# FOC-MESC_mini.net
KiCad netlist of a schematic drawn in Altium Designer
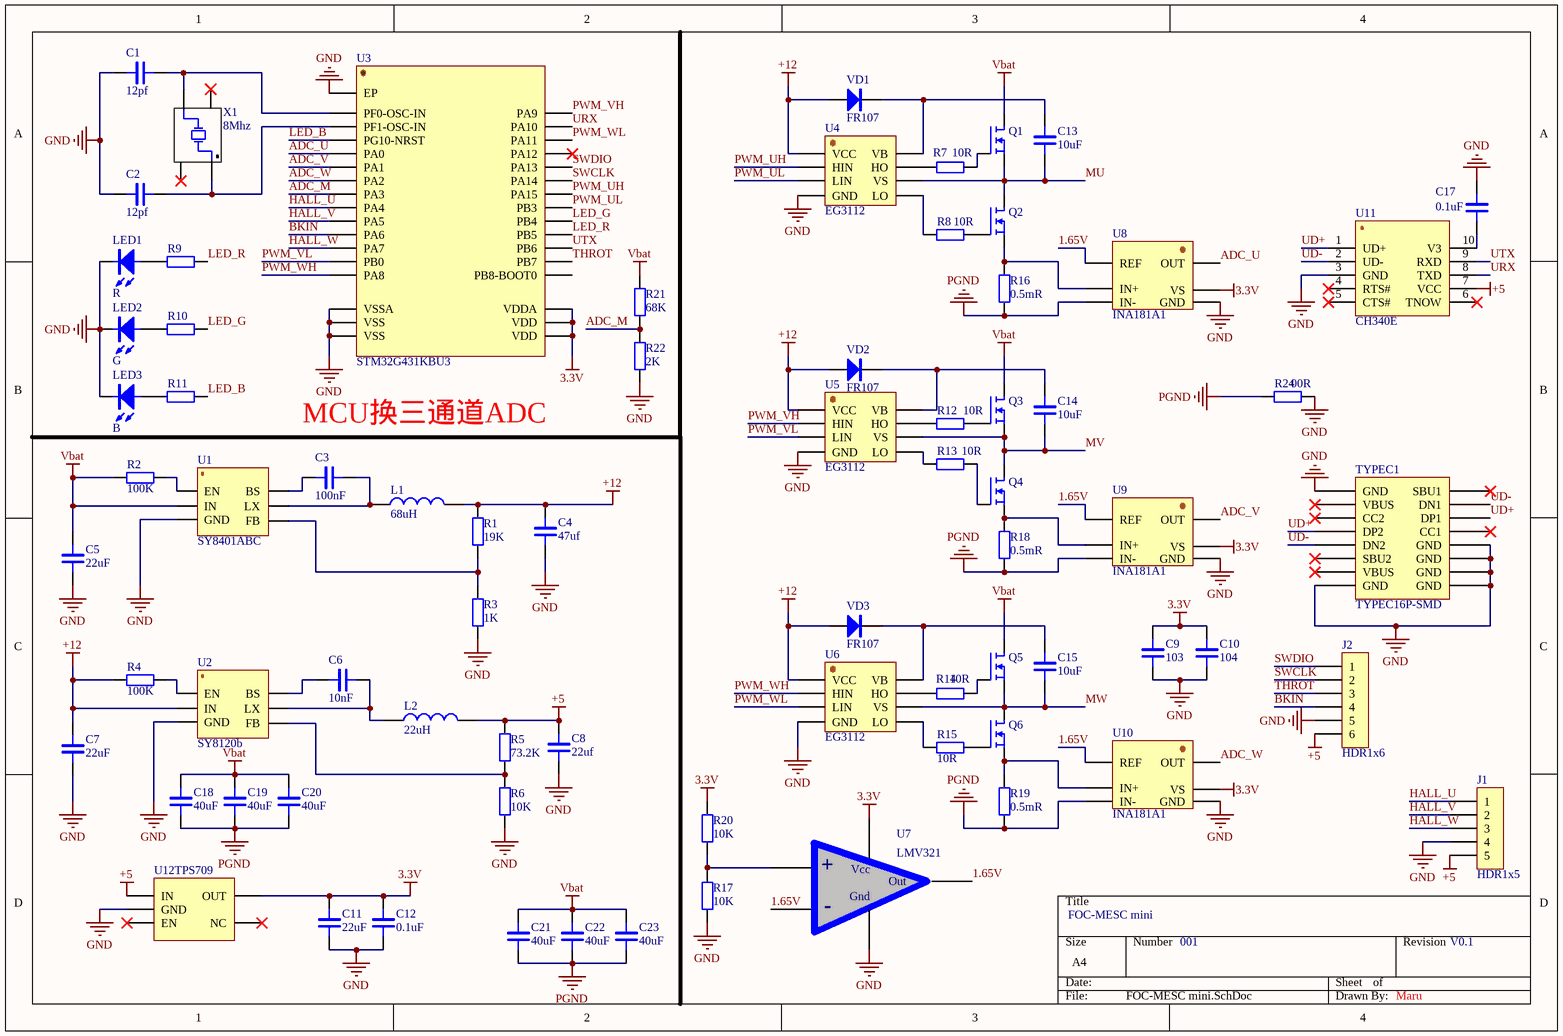
[diagram p0: FOC-MESC mini.SchDoc]

(export (version "E")
  (design (tool "Eeschema 10.0.6"))
  (components
    (comp (ref "C1")
      (value "12pf")
      (footprint "LC-0603_C")
      (description "Capacitor")
      (libsource (lib "General") (part "CAP"))
    )
    (comp (ref "C2")
      (value "12pf")
      (footprint "LC-0603_C")
      (description "Capacitor")
      (libsource (lib "General") (part "CAP"))
    )
    (comp (ref "C3")
      (value "100nF")
      (footprint "LC-0603_C")
      (description "Capacitor")
      (libsource (lib "General") (part "CAP"))
    )
    (comp (ref "C4")
      (value "47uf")
      (footprint "LC-0603_C")
      (description "Capacitor")
      (libsource (lib "General") (part "CAP"))
    )
    (comp (ref "C5")
      (value "22uF")
      (footprint "LC-0603_C")
      (description "Capacitor")
      (libsource (lib "General") (part "CAP"))
    )
    (comp (ref "C6")
      (value "10nF")
      (footprint "LC-0603_C")
      (description "Capacitor")
      (libsource (lib "General") (part "CAP"))
    )
    (comp (ref "C7")
      (value "22uF")
      (footprint "LC-0603_C")
      (description "Capacitor")
      (libsource (lib "General") (part "CAP"))
    )
    (comp (ref "C8")
      (value "22uf")
      (footprint "LC-0603_C")
      (description "Capacitor")
      (libsource (lib "General") (part "CAP"))
    )
    (comp (ref "C9")
      (value "103")
      (footprint "LC-0603_C")
      (description "Capacitor")
      (libsource (lib "General") (part "CAP"))
    )
    (comp (ref "C10")
      (value "104")
      (footprint "LC-0603_C")
      (description "Capacitor")
      (libsource (lib "General") (part "CAP"))
    )
    (comp (ref "C11")
      (value "22uF")
      (footprint "LC-0603_C")
      (description "Capacitor")
      (libsource (lib "General") (part "CAP"))
    )
    (comp (ref "C12")
      (value "0.1uF")
      (footprint "LC-0603_C")
      (description "Capacitor")
      (libsource (lib "General") (part "CAP"))
    )
    (comp (ref "C13")
      (value "10uF")
      (footprint "LC-0603_C")
      (description "Capacitor")
      (libsource (lib "General") (part "CAP"))
    )
    (comp (ref "C14")
      (value "10uF")
      (footprint "LC-0603_C")
      (description "Capacitor")
      (libsource (lib "General") (part "CAP"))
    )
    (comp (ref "C15")
      (value "10uF")
      (footprint "LC-0603_C")
      (description "Capacitor")
      (libsource (lib "General") (part "CAP"))
    )
    (comp (ref "C17")
      (value "0.1uF")
      (footprint "LC-0603_C")
      (description "Capacitor")
      (libsource (lib "General") (part "CAP"))
    )
    (comp (ref "C18")
      (value "40uF")
      (footprint "LC-1206_C")
      (description "Capacitor")
      (libsource (lib "General") (part "CAP"))
    )
    (comp (ref "C19")
      (value "40uF")
      (footprint "LC-1206_C")
      (description "Capacitor")
      (libsource (lib "General") (part "CAP"))
    )
    (comp (ref "C20")
      (value "40uF")
      (footprint "LC-1206_C")
      (description "Capacitor")
      (libsource (lib "General") (part "CAP"))
    )
    (comp (ref "C21")
      (value "40uF")
      (footprint "LC-1206_C")
      (description "Capacitor")
      (libsource (lib "General") (part "CAP"))
    )
    (comp (ref "C22")
      (value "40uF")
      (footprint "LC-1206_C")
      (description "Capacitor")
      (libsource (lib "General") (part "CAP"))
    )
    (comp (ref "C23")
      (value "40uF")
      (footprint "LC-1206_C")
      (description "Capacitor")
      (libsource (lib "General") (part "CAP"))
    )
    (comp (ref "J1")
      (value "HDR1x5")
      (footprint "HDR-1X5")
      (description "Connector")
      (libsource (lib "General") (part "HDR1x5"))
    )
    (comp (ref "J2")
      (value "HDR1x6")
      (footprint "PH2.0 S-W-6P")
      (description "Connector")
      (libsource (lib "General") (part "HDR1x6"))
    )
    (comp (ref "L1")
      (value "68uH")
      (footprint "CD31")
      (description "小功率贴片电感")
      (fields (field (name "版权归属") "源创客"))
      (libsource (lib "电阻-电容-电感") (part "L"))
    )
    (comp (ref "L2")
      (value "22uH")
      (footprint "CD31")
      (description "小功率贴片电感")
      (fields (field (name "版权归属") "源创客"))
      (libsource (lib "电阻-电容-电感") (part "L"))
    )
    (comp (ref "LED1") (value "R") (footprint "LED-0603") (libsource (lib "General") (part "LED")))
    (comp (ref "LED2")
      (value "G")
      (footprint "LED-0603")
      (description "LED")
      (libsource (lib "General") (part "LED"))
    )
    (comp (ref "LED3")
      (value "B")
      (footprint "LED-0603")
      (description "LED")
      (libsource (lib "General") (part "LED"))
    )
    (comp (ref "Q1")
      (value "N-MOSFET")
      (footprint "LC-DFN-8_5x6mm")
      (libsource (lib "General") (part "N-MOSFET"))
    )
    (comp (ref "Q2")
      (value "N-MOSFET")
      (footprint "LC-DFN-8_5x6mm")
      (libsource (lib "General") (part "N-MOSFET"))
    )
    (comp (ref "Q3")
      (value "N-MOSFET")
      (footprint "LC-DFN-8_5x6mm")
      (libsource (lib "General") (part "N-MOSFET"))
    )
    (comp (ref "Q4")
      (value "N-MOSFET")
      (footprint "LC-DFN-8_5x6mm")
      (libsource (lib "General") (part "N-MOSFET"))
    )
    (comp (ref "Q5")
      (value "N-MOSFET")
      (footprint "LC-DFN-8_5x6mm")
      (libsource (lib "General") (part "N-MOSFET"))
    )
    (comp (ref "Q6")
      (value "N-MOSFET")
      (footprint "LC-DFN-8_5x6mm")
      (libsource (lib "General") (part "N-MOSFET"))
    )
    (comp (ref "R1")
      (value "19K")
      (footprint "LC-0603_R")
      (description "Resistor")
      (libsource (lib "General") (part "RES"))
    )
    (comp (ref "R2")
      (value "100K")
      (footprint "LC-0603_R")
      (description "Resistor")
      (libsource (lib "") (part "RES_2"))
    )
    (comp (ref "R3")
      (value "1K")
      (footprint "LC-0603_R")
      (description "Resistor")
      (libsource (lib "General") (part "RES"))
    )
    (comp (ref "R4")
      (value "100K")
      (footprint "LC-0603_R")
      (description "Resistor")
      (libsource (lib "") (part "RES_2"))
    )
    (comp (ref "R5")
      (value "73.2K")
      (footprint "LC-0603_R")
      (description "Resistor")
      (libsource (lib "General") (part "RES"))
    )
    (comp (ref "R6")
      (value "10K")
      (footprint "LC-0603_R")
      (description "Resistor")
      (libsource (lib "General") (part "RES"))
    )
    (comp (ref "R7")
      (value "10R")
      (footprint "LC-0603_R")
      (description "Resistor")
      (libsource (lib "") (part "RES_1"))
    )
    (comp (ref "R8")
      (value "10R")
      (footprint "LC-0603_R")
      (description "Resistor")
      (libsource (lib "") (part "RES_1"))
    )
    (comp (ref "R9")
      (value "800R")
      (footprint "LC-0603_R")
      (description "Resistor")
      (libsource (lib "") (part "RES_1"))
    )
    (comp (ref "R10")
      (value "800R")
      (footprint "LC-0603_R")
      (description "Resistor")
      (libsource (lib "") (part "RES_1"))
    )
    (comp (ref "R11")
      (value "800R")
      (footprint "LC-0603_R")
      (description "Resistor")
      (libsource (lib "") (part "RES_1"))
    )
    (comp (ref "R12")
      (value "10R")
      (footprint "LC-0603_R")
      (description "Resistor")
      (libsource (lib "") (part "RES_1"))
    )
    (comp (ref "R13")
      (value "10R")
      (footprint "LC-0603_R")
      (description "Resistor")
      (libsource (lib "") (part "RES_1"))
    )
    (comp (ref "R14")
      (value "10R")
      (footprint "LC-0603_R")
      (description "Resistor")
      (libsource (lib "") (part "RES_1"))
    )
    (comp (ref "R15")
      (value "10R")
      (footprint "LC-0603_R")
      (description "Resistor")
      (libsource (lib "") (part "RES_1"))
    )
    (comp (ref "R16")
      (value "0.5mR")
      (footprint "LC-2512_R")
      (description "Resistor")
      (libsource (lib "General") (part "RES"))
    )
    (comp (ref "R17")
      (value "10K")
      (footprint "LC-0603_R")
      (description "Resistor")
      (libsource (lib "General") (part "RES"))
    )
    (comp (ref "R18")
      (value "0.5mR")
      (footprint "LC-2512_R")
      (description "Resistor")
      (libsource (lib "General") (part "RES"))
    )
    (comp (ref "R19")
      (value "0.5mR")
      (footprint "LC-2512_R")
      (description "Resistor")
      (libsource (lib "General") (part "RES"))
    )
    (comp (ref "R20")
      (value "10K")
      (footprint "LC-0603_R")
      (description "Resistor")
      (libsource (lib "General") (part "RES"))
    )
    (comp (ref "R21")
      (value "68K")
      (footprint "LC-0603_R")
      (description "Resistor")
      (libsource (lib "") (part "RES_3"))
    )
    (comp (ref "R22")
      (value "2K")
      (footprint "LC-0603_R")
      (description "Resistor")
      (libsource (lib "") (part "RES_3"))
    )
    (comp (ref "R24")
      (value "00R")
      (footprint "LC-1206_R")
      (description "Resistor")
      (libsource (lib "") (part "RES_1"))
    )
    (comp (ref "TYPEC1")
      (value "TYPEC16P-SMD")
      (footprint "TYPEC-16PIN DIP")
      (libsource (lib "General") (part "TYPEC16P-SMD"))
    )
    (comp (ref "U1")
      (value "SY8401ABC")
      (footprint "LC-SOT-23-6")
      (description "DC-DC")
      (libsource (lib "General") (part "SY8120b"))
    )
    (comp (ref "U2")
      (value "SY8120b")
      (footprint "LC-SOT-23-6")
      (description "DC-DC")
      (libsource (lib "General") (part "SY8120b"))
    )
    (comp (ref "U3")
      (value "STM32G431KBU3")
      (footprint "LC-QFN-32_7x7x065P")
      (libsource (lib "STM32系列单片机") (part "STM32G431KBU3"))
    )
    (comp (ref "U4")
      (value "EG3112")
      (footprint "LC-SOIC-8_150mil")
      (libsource (lib "General") (part "EG3112"))
    )
    (comp (ref "U5")
      (value "EG3112")
      (footprint "LC-SOIC-8_150mil")
      (libsource (lib "General") (part "EG3112"))
    )
    (comp (ref "U6")
      (value "EG3112")
      (footprint "LC-SOIC-8_150mil")
      (libsource (lib "General") (part "EG3112"))
    )
    (comp (ref "U7")
      (value "LMV321")
      (footprint "LC-SOT-23-5")
      (libsource (lib "General") (part "OPA-Single"))
    )
    (comp (ref "U8")
      (value "INA181A1")
      (footprint "LC-SOT-23-6")
      (description "40 倍")
      (libsource (lib "General") (part "INA181A1"))
    )
    (comp (ref "U9")
      (value "INA181A1")
      (footprint "LC-SOT-23-6")
      (description "40 倍")
      (libsource (lib "General") (part "INA181A1"))
    )
    (comp (ref "U10")
      (value "INA181A1")
      (footprint "LC-SOT-23-6")
      (description "40 倍")
      (libsource (lib "General") (part "INA181A1"))
    )
    (comp (ref "U11") (value "CH340E") (footprint "LC-MSOP-10") (libsource (lib "General") (part "CH340E")))
    (comp (ref "U12") (value "TPS709") (footprint "LC-SOT-23-5") (libsource (lib "General") (part "TPS709")))
    (comp (ref "VD1")
      (value "FR107")
      (footprint "LC-SOD-123F")
      (description "快恢复整流二极管")
      (fields (field (name "版权归属") "源创客"))
      (libsource (lib "二极管-整流桥") (part "FR107"))
    )
    (comp (ref "VD2")
      (value "FR107")
      (footprint "LC-SOD-123F")
      (description "快恢复整流二极管")
      (fields (field (name "版权归属") "源创客"))
      (libsource (lib "二极管-整流桥") (part "FR107"))
    )
    (comp (ref "VD3")
      (value "FR107")
      (footprint "LC-SOD-123F")
      (description "快恢复整流二极管")
      (fields (field (name "版权归属") "源创客"))
      (libsource (lib "二极管-整流桥") (part "FR107"))
    )
    (comp (ref "X1")
      (value "8Mhz")
      (footprint "XTAL-5.0X3.2")
      (libsource (lib "General") (part "XTAL-4 Crystal"))
    )
  )
  (nets
    (net (code "1") (name "+5") (class "Default")
      (node (ref "C8") (pin "1") (pinfunction "1_1") (pintype "passive"))
      (node (ref "J1") (pin "5") (pinfunction "5_5") (pintype "passive"))
      (node (ref "J2") (pin "6") (pinfunction "6_6") (pintype "passive"))
      (node (ref "L2") (pin "2") (pinfunction "2_2") (pintype "passive"))
      (node (ref "R5") (pin "2") (pinfunction "2_2") (pintype "passive"))
      (node (ref "U11") (pin "7") (pinfunction "VCC_7") (pintype "passive"))
      (node (ref "U12") (pin "1") (pinfunction "IN_1") (pintype "passive"))
    )
    (net (code "2") (name "+12") (class "Default")
      (node (ref "C4") (pin "2") (pinfunction "2_2") (pintype "passive"))
      (node (ref "C7") (pin "2") (pinfunction "2_2") (pintype "passive"))
      (node (ref "L1") (pin "2") (pinfunction "2_2") (pintype "passive"))
      (node (ref "R1") (pin "2") (pinfunction "2_2") (pintype "passive"))
      (node (ref "R4") (pin "1") (pinfunction "1_1") (pintype "passive"))
      (node (ref "U2") (pin "5") (pinfunction "IN_5") (pintype "passive"))
      (node (ref "U4") (pin "1") (pinfunction "VCC_1") (pintype "passive"))
      (node (ref "U5") (pin "1") (pinfunction "VCC_1") (pintype "passive"))
      (node (ref "U6") (pin "1") (pinfunction "VCC_1") (pintype "passive"))
      (node (ref "VD1") (pin "1") (pinfunction "A_1") (pintype "passive"))
      (node (ref "VD2") (pin "1") (pinfunction "A_1") (pintype "passive"))
      (node (ref "VD3") (pin "1") (pinfunction "A_1") (pintype "passive"))
    )
    (net (code "3") (name "/1.65V") (class "Default")
      (node (ref "U10") (pin "5") (pinfunction "REF_5") (pintype "passive"))
      (node (ref "U7") (pin "1") (pintype "passive"))
      (node (ref "U7") (pin "4") (pintype "passive"))
      (node (ref "U8") (pin "5") (pinfunction "REF_5") (pintype "passive"))
      (node (ref "U9") (pin "5") (pinfunction "REF_5") (pintype "passive"))
    )
    (net (code "4") (name "/ADC_M") (class "Default")
      (node (ref "R21") (pin "2") (pinfunction "2_2") (pintype "passive"))
      (node (ref "R22") (pin "1") (pinfunction "1_1") (pintype "passive"))
      (node (ref "U3") (pin "8") (pinfunction "PA3_8") (pintype "passive"))
    )
    (net (code "5") (name "/ADC_U") (class "Default")
      (node (ref "U3") (pin "5") (pinfunction "PA0_5") (pintype "passive"))
      (node (ref "U8") (pin "1") (pinfunction "OUT_1") (pintype "passive"))
    )
    (net (code "6") (name "/ADC_V") (class "Default")
      (node (ref "U3") (pin "6") (pinfunction "PA1_6") (pintype "passive"))
      (node (ref "U9") (pin "1") (pinfunction "OUT_1") (pintype "passive"))
    )
    (net (code "7") (name "/ADC_W") (class "Default")
      (node (ref "U10") (pin "1") (pinfunction "OUT_1") (pintype "passive"))
      (node (ref "U3") (pin "7") (pinfunction "PA2_7") (pintype "passive"))
    )
    (net (code "8") (name "/BKIN") (class "Default")
      (node (ref "J2") (pin "4") (pinfunction "4_4") (pintype "passive"))
      (node (ref "U3") (pin "11") (pinfunction "PA6_11") (pintype "passive"))
    )
    (net (code "9") (name "/HALL_U") (class "Default")
      (node (ref "J1") (pin "1") (pinfunction "1_1") (pintype "passive"))
      (node (ref "U3") (pin "9") (pinfunction "PA4_9") (pintype "passive"))
    )
    (net (code "10") (name "/HALL_V") (class "Default")
      (node (ref "J1") (pin "2") (pinfunction "2_2") (pintype "passive"))
      (node (ref "U3") (pin "10") (pinfunction "PA5_10") (pintype "passive"))
    )
    (net (code "11") (name "/HALL_W") (class "Default")
      (node (ref "J1") (pin "3") (pinfunction "3_3") (pintype "passive"))
      (node (ref "U3") (pin "12") (pinfunction "PA7_12") (pintype "passive"))
    )
    (net (code "12") (name "/LED_B") (class "Default")
      (node (ref "R11") (pin "1") (pinfunction "1_1") (pintype "passive"))
      (node (ref "U3") (pin "4") (pinfunction "PG10-NRST_4") (pintype "passive"))
    )
    (net (code "13") (name "/LED_G") (class "Default")
      (node (ref "R10") (pin "1") (pinfunction "1_1") (pintype "passive"))
      (node (ref "U3") (pin "27") (pinfunction "PB4_27") (pintype "passive"))
    )
    (net (code "14") (name "/LED_R") (class "Default")
      (node (ref "R9") (pin "1") (pinfunction "1_1") (pintype "passive"))
      (node (ref "U3") (pin "28") (pinfunction "PB5_28") (pintype "passive"))
    )
    (net (code "15") (name "/MU") (class "Default")
      (node (ref "C13") (pin "1") (pinfunction "1_1") (pintype "passive"))
      (node (ref "Q1") (pin "3") (pinfunction "S_3") (pintype "passive"))
      (node (ref "Q2") (pin "2") (pinfunction "D_2") (pintype "passive"))
      (node (ref "U4") (pin "6") (pinfunction "VS_6") (pintype "passive"))
    )
    (net (code "16") (name "/MV") (class "Default")
      (node (ref "C14") (pin "1") (pinfunction "1_1") (pintype "passive"))
      (node (ref "Q3") (pin "3") (pinfunction "S_3") (pintype "passive"))
      (node (ref "Q4") (pin "2") (pinfunction "D_2") (pintype "passive"))
      (node (ref "U5") (pin "6") (pinfunction "VS_6") (pintype "passive"))
    )
    (net (code "17") (name "/MW") (class "Default")
      (node (ref "C15") (pin "1") (pinfunction "1_1") (pintype "passive"))
      (node (ref "Q5") (pin "3") (pinfunction "S_3") (pintype "passive"))
      (node (ref "Q6") (pin "2") (pinfunction "D_2") (pintype "passive"))
      (node (ref "U6") (pin "6") (pinfunction "VS_6") (pintype "passive"))
    )
    (net (code "18") (name "/PWM_UH") (class "Default")
      (node (ref "U3") (pin "25") (pinfunction "PA15_25") (pintype "passive"))
      (node (ref "U4") (pin "2") (pinfunction "HIN_2") (pintype "passive"))
    )
    (net (code "19") (name "/PWM_UL") (class "Default")
      (node (ref "U3") (pin "26") (pinfunction "PB3_26") (pintype "passive"))
      (node (ref "U4") (pin "3") (pinfunction "LIN_3") (pintype "passive"))
    )
    (net (code "20") (name "/PWM_VH") (class "Default")
      (node (ref "U3") (pin "19") (pinfunction "PA9_19") (pintype "passive"))
      (node (ref "U5") (pin "2") (pinfunction "HIN_2") (pintype "passive"))
    )
    (net (code "21") (name "/PWM_VL") (class "Default")
      (node (ref "U3") (pin "13") (pinfunction "PB0_13") (pintype "passive"))
      (node (ref "U5") (pin "3") (pinfunction "LIN_3") (pintype "passive"))
    )
    (net (code "22") (name "/PWM_WH") (class "Default")
      (node (ref "U3") (pin "18") (pinfunction "PA8_18") (pintype "passive"))
      (node (ref "U6") (pin "2") (pinfunction "HIN_2") (pintype "passive"))
    )
    (net (code "23") (name "/PWM_WL") (class "Default")
      (node (ref "U3") (pin "21") (pinfunction "PA11_21") (pintype "passive"))
      (node (ref "U6") (pin "3") (pinfunction "LIN_3") (pintype "passive"))
    )
    (net (code "24") (name "/SWCLK") (class "Default")
      (node (ref "J2") (pin "2") (pinfunction "2_2") (pintype "passive"))
      (node (ref "U3") (pin "24") (pinfunction "PA14_24") (pintype "passive"))
    )
    (net (code "25") (name "/SWDIO") (class "Default")
      (node (ref "J2") (pin "1") (pinfunction "1_1") (pintype "passive"))
      (node (ref "U3") (pin "23") (pinfunction "PA13_23") (pintype "passive"))
    )
    (net (code "26") (name "/THROT") (class "Default")
      (node (ref "J2") (pin "3") (pinfunction "3_3") (pintype "passive"))
      (node (ref "U3") (pin "30") (pinfunction "PB7_30") (pintype "passive"))
    )
    (net (code "27") (name "/UD+") (class "Default")
      (node (ref "TYPEC1") (pin "A6") (pinfunction "DP1_A6") (pintype "passive"))
      (node (ref "TYPEC1") (pin "B6") (pinfunction "DP2_B6") (pintype "passive"))
      (node (ref "U11") (pin "1") (pinfunction "UD+_1") (pintype "passive"))
    )
    (net (code "28") (name "/UD-") (class "Default")
      (node (ref "TYPEC1") (pin "A7") (pinfunction "DN1_A7") (pintype "passive"))
      (node (ref "TYPEC1") (pin "B7") (pinfunction "DN2_B7") (pintype "passive"))
      (node (ref "U11") (pin "2") (pinfunction "UD-_2") (pintype "passive"))
    )
    (net (code "29") (name "/URX") (class "Default")
      (node (ref "U11") (pin "8") (pinfunction "TXD_8") (pintype "passive"))
      (node (ref "U3") (pin "20") (pinfunction "PA10_20") (pintype "passive"))
    )
    (net (code "30") (name "/UTX") (class "Default")
      (node (ref "U11") (pin "9") (pinfunction "RXD_9") (pintype "passive"))
      (node (ref "U3") (pin "29") (pinfunction "PB6_29") (pintype "passive"))
    )
    (net (code "31") (name "3.3V") (class "Default")
      (node (ref "C10") (pin "2") (pinfunction "2_2") (pintype "passive"))
      (node (ref "C11") (pin "2") (pinfunction "2_2") (pintype "passive"))
      (node (ref "C12") (pin "2") (pinfunction "2_2") (pintype "passive"))
      (node (ref "C9") (pin "2") (pinfunction "2_2") (pintype "passive"))
      (node (ref "R20") (pin "2") (pinfunction "2_2") (pintype "passive"))
      (node (ref "U10") (pin "6") (pinfunction "VS_6") (pintype "passive"))
      (node (ref "U12") (pin "5") (pinfunction "OUT_5") (pintype "passive"))
      (node (ref "U3") (pin "1") (pinfunction "VDD_1") (pintype "passive"))
      (node (ref "U3") (pin "15") (pinfunction "VDDA_15") (pintype "passive"))
      (node (ref "U3") (pin "17") (pinfunction "VDD_17") (pintype "passive"))
      (node (ref "U7") (pin "5") (pintype "passive"))
      (node (ref "U8") (pin "6") (pinfunction "VS_6") (pintype "passive"))
      (node (ref "U9") (pin "6") (pinfunction "VS_6") (pintype "passive"))
    )
    (net (code "32") (name "GND") (class "Default")
      (node (ref "C1") (pin "1") (pinfunction "1_1") (pintype "passive"))
      (node (ref "C10") (pin "1") (pinfunction "1_1") (pintype "passive"))
      (node (ref "C11") (pin "1") (pinfunction "1_1") (pintype "passive"))
      (node (ref "C12") (pin "1") (pinfunction "1_1") (pintype "passive"))
      (node (ref "C17") (pin "2") (pinfunction "2_2") (pintype "passive"))
      (node (ref "C2") (pin "1") (pinfunction "1_1") (pintype "passive"))
      (node (ref "C4") (pin "1") (pinfunction "1_1") (pintype "passive"))
      (node (ref "C5") (pin "1") (pinfunction "1_1") (pintype "passive"))
      (node (ref "C7") (pin "1") (pinfunction "1_1") (pintype "passive"))
      (node (ref "C8") (pin "2") (pinfunction "2_2") (pintype "passive"))
      (node (ref "C9") (pin "1") (pinfunction "1_1") (pintype "passive"))
      (node (ref "J1") (pin "4") (pinfunction "4_4") (pintype "passive"))
      (node (ref "J2") (pin "5") (pinfunction "5_5") (pintype "passive"))
      (node (ref "LED1") (pin "2") (pinfunction "C_2") (pintype "passive"))
      (node (ref "LED2") (pin "2") (pinfunction "C_2") (pintype "passive"))
      (node (ref "LED3") (pin "2") (pinfunction "C_2") (pintype "passive"))
      (node (ref "R17") (pin "1") (pinfunction "1_1") (pintype "passive"))
      (node (ref "R22") (pin "2") (pinfunction "2_2") (pintype "passive"))
      (node (ref "R24") (pin "1") (pinfunction "1_1") (pintype "passive"))
      (node (ref "R3") (pin "1") (pinfunction "1_1") (pintype "passive"))
      (node (ref "R6") (pin "1") (pinfunction "1_1") (pintype "passive"))
      (node (ref "TYPEC1") (pin "13") (pinfunction "GND_13") (pintype "passive"))
      (node (ref "TYPEC1") (pin "14") (pinfunction "GND_14") (pintype "passive"))
      (node (ref "TYPEC1") (pin "15") (pinfunction "GND_15") (pintype "passive"))
      (node (ref "TYPEC1") (pin "16") (pinfunction "GND_16") (pintype "passive"))
      (node (ref "TYPEC1") (pin "A1B12") (pinfunction "GND_A1B12") (pintype "passive"))
      (node (ref "TYPEC1") (pin "B1A12") (pinfunction "GND_B1A12") (pintype "passive"))
      (node (ref "U1") (pin "2") (pinfunction "GND_2") (pintype "passive"))
      (node (ref "U10") (pin "2") (pinfunction "GND_2") (pintype "passive"))
      (node (ref "U11") (pin "3") (pinfunction "GND_3") (pintype "passive"))
      (node (ref "U12") (pin "2") (pinfunction "GND_2") (pintype "passive"))
      (node (ref "U2") (pin "2") (pinfunction "GND_2") (pintype "passive"))
      (node (ref "U3") (pin "0") (pinfunction "EP_0") (pintype "passive"))
      (node (ref "U3") (pin "14") (pinfunction "VSSA_14") (pintype "passive"))
      (node (ref "U3") (pin "16") (pinfunction "VSS_16") (pintype "passive"))
      (node (ref "U3") (pin "32") (pinfunction "VSS_32") (pintype "passive"))
      (node (ref "U4") (pin "4") (pinfunction "GND_4") (pintype "passive"))
      (node (ref "U5") (pin "4") (pinfunction "GND_4") (pintype "passive"))
      (node (ref "U6") (pin "4") (pinfunction "GND_4") (pintype "passive"))
      (node (ref "U7") (pin "2") (pinfunction "VSS_2") (pintype "passive"))
      (node (ref "U8") (pin "2") (pinfunction "GND_2") (pintype "passive"))
      (node (ref "U9") (pin "2") (pinfunction "GND_2") (pintype "passive"))
    )
    (net (code "33") (name "Net-(LED1-A)") (class "Default")
      (node (ref "LED1") (pin "1") (pinfunction "A_1") (pintype "passive"))
      (node (ref "R9") (pin "2") (pinfunction "2_2") (pintype "passive"))
    )
    (net (code "34") (name "Net-(LED2-A)") (class "Default")
      (node (ref "LED2") (pin "1") (pinfunction "A_1") (pintype "passive"))
      (node (ref "R10") (pin "2") (pinfunction "2_2") (pintype "passive"))
    )
    (net (code "35") (name "Net-(LED3-A)") (class "Default")
      (node (ref "LED3") (pin "1") (pinfunction "A_1") (pintype "passive"))
      (node (ref "R11") (pin "2") (pinfunction "2_2") (pintype "passive"))
    )
    (net (code "36") (name "Net-(Q1-G)") (class "Default")
      (node (ref "Q1") (pin "1") (pinfunction "G_1") (pintype "passive"))
      (node (ref "R7") (pin "1") (pinfunction "1_1") (pintype "passive"))
    )
    (net (code "37") (name "Net-(Q2-G)") (class "Default")
      (node (ref "Q2") (pin "1") (pinfunction "G_1") (pintype "passive"))
      (node (ref "R8") (pin "1") (pinfunction "1_1") (pintype "passive"))
    )
    (net (code "38") (name "Net-(Q2-S)") (class "Default")
      (node (ref "Q2") (pin "3") (pinfunction "S_3") (pintype "passive"))
      (node (ref "R16") (pin "2") (pinfunction "2_2") (pintype "passive"))
      (node (ref "U8") (pin "3") (pinfunction "IN+_3") (pintype "passive"))
    )
    (net (code "39") (name "Net-(Q3-G)") (class "Default")
      (node (ref "Q3") (pin "1") (pinfunction "G_1") (pintype "passive"))
      (node (ref "R12") (pin "1") (pinfunction "1_1") (pintype "passive"))
    )
    (net (code "40") (name "Net-(Q4-G)") (class "Default")
      (node (ref "Q4") (pin "1") (pinfunction "G_1") (pintype "passive"))
      (node (ref "R13") (pin "1") (pinfunction "1_1") (pintype "passive"))
    )
    (net (code "41") (name "Net-(Q4-S)") (class "Default")
      (node (ref "Q4") (pin "3") (pinfunction "S_3") (pintype "passive"))
      (node (ref "R18") (pin "2") (pinfunction "2_2") (pintype "passive"))
      (node (ref "U9") (pin "3") (pinfunction "IN+_3") (pintype "passive"))
    )
    (net (code "42") (name "Net-(Q5-G)") (class "Default")
      (node (ref "Q5") (pin "1") (pinfunction "G_1") (pintype "passive"))
      (node (ref "R14") (pin "1") (pinfunction "1_1") (pintype "passive"))
    )
    (net (code "43") (name "Net-(Q6-G)") (class "Default")
      (node (ref "Q6") (pin "1") (pinfunction "G_1") (pintype "passive"))
      (node (ref "R15") (pin "1") (pinfunction "1_1") (pintype "passive"))
    )
    (net (code "44") (name "Net-(Q6-S)") (class "Default")
      (node (ref "Q6") (pin "3") (pinfunction "S_3") (pintype "passive"))
      (node (ref "R19") (pin "2") (pinfunction "2_2") (pintype "passive"))
      (node (ref "U10") (pin "3") (pinfunction "IN+_3") (pintype "passive"))
    )
    (net (code "45") (name "Net-(R17-Pad2)") (class "Default")
      (node (ref "R17") (pin "2") (pinfunction "2_2") (pintype "passive"))
      (node (ref "R20") (pin "1") (pinfunction "1_1") (pintype "passive"))
      (node (ref "U7") (pin "3") (pintype "passive"))
    )
    (net (code "46") (name "Net-(U1-BS)") (class "Default")
      (node (ref "C3") (pin "2") (pinfunction "2_2") (pintype "passive"))
      (node (ref "U1") (pin "1") (pinfunction "BS_1") (pintype "passive"))
    )
    (net (code "47") (name "Net-(U1-EN)") (class "Default")
      (node (ref "R2") (pin "2") (pinfunction "2_2") (pintype "passive"))
      (node (ref "U1") (pin "4") (pinfunction "EN_4") (pintype "passive"))
    )
    (net (code "48") (name "Net-(U1-FB)") (class "Default")
      (node (ref "R1") (pin "1") (pinfunction "1_1") (pintype "passive"))
      (node (ref "R3") (pin "2") (pinfunction "2_2") (pintype "passive"))
      (node (ref "U1") (pin "3") (pinfunction "FB_3") (pintype "passive"))
    )
    (net (code "49") (name "Net-(U1-LX)") (class "Default")
      (node (ref "C3") (pin "1") (pinfunction "1_1") (pintype "passive"))
      (node (ref "L1") (pin "1") (pinfunction "1_1") (pintype "passive"))
      (node (ref "U1") (pin "6") (pinfunction "LX_6") (pintype "passive"))
    )
    (net (code "50") (name "Net-(U2-BS)") (class "Default")
      (node (ref "C6") (pin "2") (pinfunction "2_2") (pintype "passive"))
      (node (ref "U2") (pin "1") (pinfunction "BS_1") (pintype "passive"))
    )
    (net (code "51") (name "Net-(U2-EN)") (class "Default")
      (node (ref "R4") (pin "2") (pinfunction "2_2") (pintype "passive"))
      (node (ref "U2") (pin "4") (pinfunction "EN_4") (pintype "passive"))
    )
    (net (code "52") (name "Net-(U2-FB)") (class "Default")
      (node (ref "R5") (pin "1") (pinfunction "1_1") (pintype "passive"))
      (node (ref "R6") (pin "2") (pinfunction "2_2") (pintype "passive"))
      (node (ref "U2") (pin "3") (pinfunction "FB_3") (pintype "passive"))
    )
    (net (code "53") (name "Net-(U2-LX)") (class "Default")
      (node (ref "C6") (pin "1") (pinfunction "1_1") (pintype "passive"))
      (node (ref "L2") (pin "1") (pinfunction "1_1") (pintype "passive"))
      (node (ref "U2") (pin "6") (pinfunction "LX_6") (pintype "passive"))
    )
    (net (code "54") (name "Net-(U3-PF0-OSC-IN)") (class "Default")
      (node (ref "C1") (pin "2") (pinfunction "2_2") (pintype "passive"))
      (node (ref "U3") (pin "2") (pinfunction "PF0-OSC-IN_2") (pintype "passive"))
      (node (ref "X1") (pin "3") (pinfunction "OSC_3") (pintype "passive"))
    )
    (net (code "55") (name "Net-(U3-PF1-OSC-IN)") (class "Default")
      (node (ref "C2") (pin "2") (pinfunction "2_2") (pintype "passive"))
      (node (ref "U3") (pin "3") (pinfunction "PF1-OSC-IN_3") (pintype "passive"))
      (node (ref "X1") (pin "1") (pinfunction "OSC_1") (pintype "passive"))
    )
    (net (code "56") (name "Net-(U4-HO)") (class "Default")
      (node (ref "R7") (pin "2") (pinfunction "2_2") (pintype "passive"))
      (node (ref "U4") (pin "7") (pinfunction "HO_7") (pintype "passive"))
    )
    (net (code "57") (name "Net-(U4-LO)") (class "Default")
      (node (ref "R8") (pin "2") (pinfunction "2_2") (pintype "passive"))
      (node (ref "U4") (pin "5") (pinfunction "LO_5") (pintype "passive"))
    )
    (net (code "58") (name "Net-(U4-VB)") (class "Default")
      (node (ref "C13") (pin "2") (pinfunction "2_2") (pintype "passive"))
      (node (ref "U4") (pin "8") (pinfunction "VB_8") (pintype "passive"))
      (node (ref "VD1") (pin "2") (pinfunction "K_2") (pintype "passive"))
    )
    (net (code "59") (name "Net-(U5-HO)") (class "Default")
      (node (ref "R12") (pin "2") (pinfunction "2_2") (pintype "passive"))
      (node (ref "U5") (pin "7") (pinfunction "HO_7") (pintype "passive"))
    )
    (net (code "60") (name "Net-(U5-LO)") (class "Default")
      (node (ref "R13") (pin "2") (pinfunction "2_2") (pintype "passive"))
      (node (ref "U5") (pin "5") (pinfunction "LO_5") (pintype "passive"))
    )
    (net (code "61") (name "Net-(U5-VB)") (class "Default")
      (node (ref "C14") (pin "2") (pinfunction "2_2") (pintype "passive"))
      (node (ref "U5") (pin "8") (pinfunction "VB_8") (pintype "passive"))
      (node (ref "VD2") (pin "2") (pinfunction "K_2") (pintype "passive"))
    )
    (net (code "62") (name "Net-(U6-HO)") (class "Default")
      (node (ref "R14") (pin "2") (pinfunction "2_2") (pintype "passive"))
      (node (ref "U6") (pin "7") (pinfunction "HO_7") (pintype "passive"))
    )
    (net (code "63") (name "Net-(U6-LO)") (class "Default")
      (node (ref "R15") (pin "2") (pinfunction "2_2") (pintype "passive"))
      (node (ref "U6") (pin "5") (pinfunction "LO_5") (pintype "passive"))
    )
    (net (code "64") (name "Net-(U6-VB)") (class "Default")
      (node (ref "C15") (pin "2") (pinfunction "2_2") (pintype "passive"))
      (node (ref "U6") (pin "8") (pinfunction "VB_8") (pintype "passive"))
      (node (ref "VD3") (pin "2") (pinfunction "K_2") (pintype "passive"))
    )
    (net (code "65") (name "Net-(U11-V3)") (class "Default")
      (node (ref "C17") (pin "1") (pinfunction "1_1") (pintype "passive"))
      (node (ref "U11") (pin "10") (pinfunction "V3_10") (pintype "passive"))
    )
    (net (code "66") (name "PGND") (class "Default")
      (node (ref "C18") (pin "1") (pinfunction "1_1") (pintype "passive"))
      (node (ref "C19") (pin "1") (pinfunction "1_1") (pintype "passive"))
      (node (ref "C20") (pin "1") (pinfunction "1_1") (pintype "passive"))
      (node (ref "C21") (pin "1") (pinfunction "1_1") (pintype "passive"))
      (node (ref "C22") (pin "1") (pinfunction "1_1") (pintype "passive"))
      (node (ref "C23") (pin "1") (pinfunction "1_1") (pintype "passive"))
      (node (ref "R16") (pin "1") (pinfunction "1_1") (pintype "passive"))
      (node (ref "R18") (pin "1") (pinfunction "1_1") (pintype "passive"))
      (node (ref "R19") (pin "1") (pinfunction "1_1") (pintype "passive"))
      (node (ref "R24") (pin "2") (pinfunction "2_2") (pintype "passive"))
      (node (ref "U10") (pin "4") (pinfunction "IN-_4") (pintype "passive"))
      (node (ref "U8") (pin "4") (pinfunction "IN-_4") (pintype "passive"))
      (node (ref "U9") (pin "4") (pinfunction "IN-_4") (pintype "passive"))
    )
    (net (code "67") (name "Vbat") (class "Default")
      (node (ref "C18") (pin "2") (pinfunction "2_2") (pintype "passive"))
      (node (ref "C19") (pin "2") (pinfunction "2_2") (pintype "passive"))
      (node (ref "C20") (pin "2") (pinfunction "2_2") (pintype "passive"))
      (node (ref "C21") (pin "2") (pinfunction "2_2") (pintype "passive"))
      (node (ref "C22") (pin "2") (pinfunction "2_2") (pintype "passive"))
      (node (ref "C23") (pin "2") (pinfunction "2_2") (pintype "passive"))
      (node (ref "C5") (pin "2") (pinfunction "2_2") (pintype "passive"))
      (node (ref "Q1") (pin "2") (pinfunction "D_2") (pintype "passive"))
      (node (ref "Q3") (pin "2") (pinfunction "D_2") (pintype "passive"))
      (node (ref "Q5") (pin "2") (pinfunction "D_2") (pintype "passive"))
      (node (ref "R2") (pin "1") (pinfunction "1_1") (pintype "passive"))
      (node (ref "R21") (pin "1") (pinfunction "1_1") (pintype "passive"))
      (node (ref "U1") (pin "5") (pinfunction "IN_5") (pintype "passive"))
    )
    (net (code "68") (name "unconnected-(TYPEC1-CC1-PadA5)") (class "Default")
      (node (ref "TYPEC1") (pin "A5") (pinfunction "CC1_A5") (pintype "passive+no_connect"))
    )
    (net (code "69") (name "unconnected-(TYPEC1-CC2-PadB5)") (class "Default")
      (node (ref "TYPEC1") (pin "B5") (pinfunction "CC2_B5") (pintype "passive+no_connect"))
    )
    (net (code "70") (name "unconnected-(TYPEC1-SBU1-PadA8)") (class "Default")
      (node (ref "TYPEC1") (pin "A8") (pinfunction "SBU1_A8") (pintype "passive+no_connect"))
    )
    (net (code "71") (name "unconnected-(TYPEC1-SBU2-PadB8)") (class "Default")
      (node (ref "TYPEC1") (pin "B8") (pinfunction "SBU2_B8") (pintype "passive+no_connect"))
    )
    (net (code "72") (name "unconnected-(TYPEC1-VBUS-PadA4B9)") (class "Default")
      (node (ref "TYPEC1") (pin "A4B9") (pinfunction "VBUS_A4B9") (pintype "passive+no_connect"))
    )
    (net (code "73") (name "unconnected-(TYPEC1-VBUS-PadB4A9)") (class "Default")
      (node (ref "TYPEC1") (pin "B4A9") (pinfunction "VBUS_B4A9") (pintype "passive+no_connect"))
    )
    (net (code "74") (name "unconnected-(U3-PA12-Pad22)") (class "Default")
      (node (ref "U3") (pin "22") (pinfunction "PA12_22") (pintype "passive+no_connect"))
    )
    (net (code "75") (name "unconnected-(U3-PB8-BOOT0-Pad31)") (class "Default")
      (node (ref "U3") (pin "31") (pinfunction "PB8-BOOT0_31") (pintype "passive"))
    )
    (net (code "76") (name "unconnected-(U11-CTS#-Pad5)") (class "Default")
      (node (ref "U11") (pin "5") (pinfunction "CTS#_5") (pintype "passive+no_connect"))
    )
    (net (code "77") (name "unconnected-(U11-RTS#-Pad4)") (class "Default")
      (node (ref "U11") (pin "4") (pinfunction "RTS#_4") (pintype "passive+no_connect"))
    )
    (net (code "78") (name "unconnected-(U11-TNOW-Pad6)") (class "Default")
      (node (ref "U11") (pin "6") (pinfunction "TNOW_6") (pintype "passive+no_connect"))
    )
    (net (code "79") (name "unconnected-(U12-EN-Pad3)") (class "Default")
      (node (ref "U12") (pin "3") (pinfunction "EN_3") (pintype "passive+no_connect"))
    )
    (net (code "80") (name "unconnected-(U12-NC-Pad4)") (class "Default")
      (node (ref "U12") (pin "4") (pinfunction "NC_4") (pintype "passive+no_connect"))
    )
    (net (code "81") (name "unconnected-(X1-11-Pad2)") (class "Default")
      (node (ref "X1") (pin "2") (pinfunction "11_2") (pintype "passive+no_connect"))
    )
    (net (code "82") (name "unconnected-(X1-OSC-Pad4)") (class "Default")
      (node (ref "X1") (pin "4") (pinfunction "OSC_4") (pintype "passive+no_connect"))
    )
  )
)
